# 4_Wifi_ESP32_Antenna.net
KiCad netlist of a schematic drawn in Altium Designer
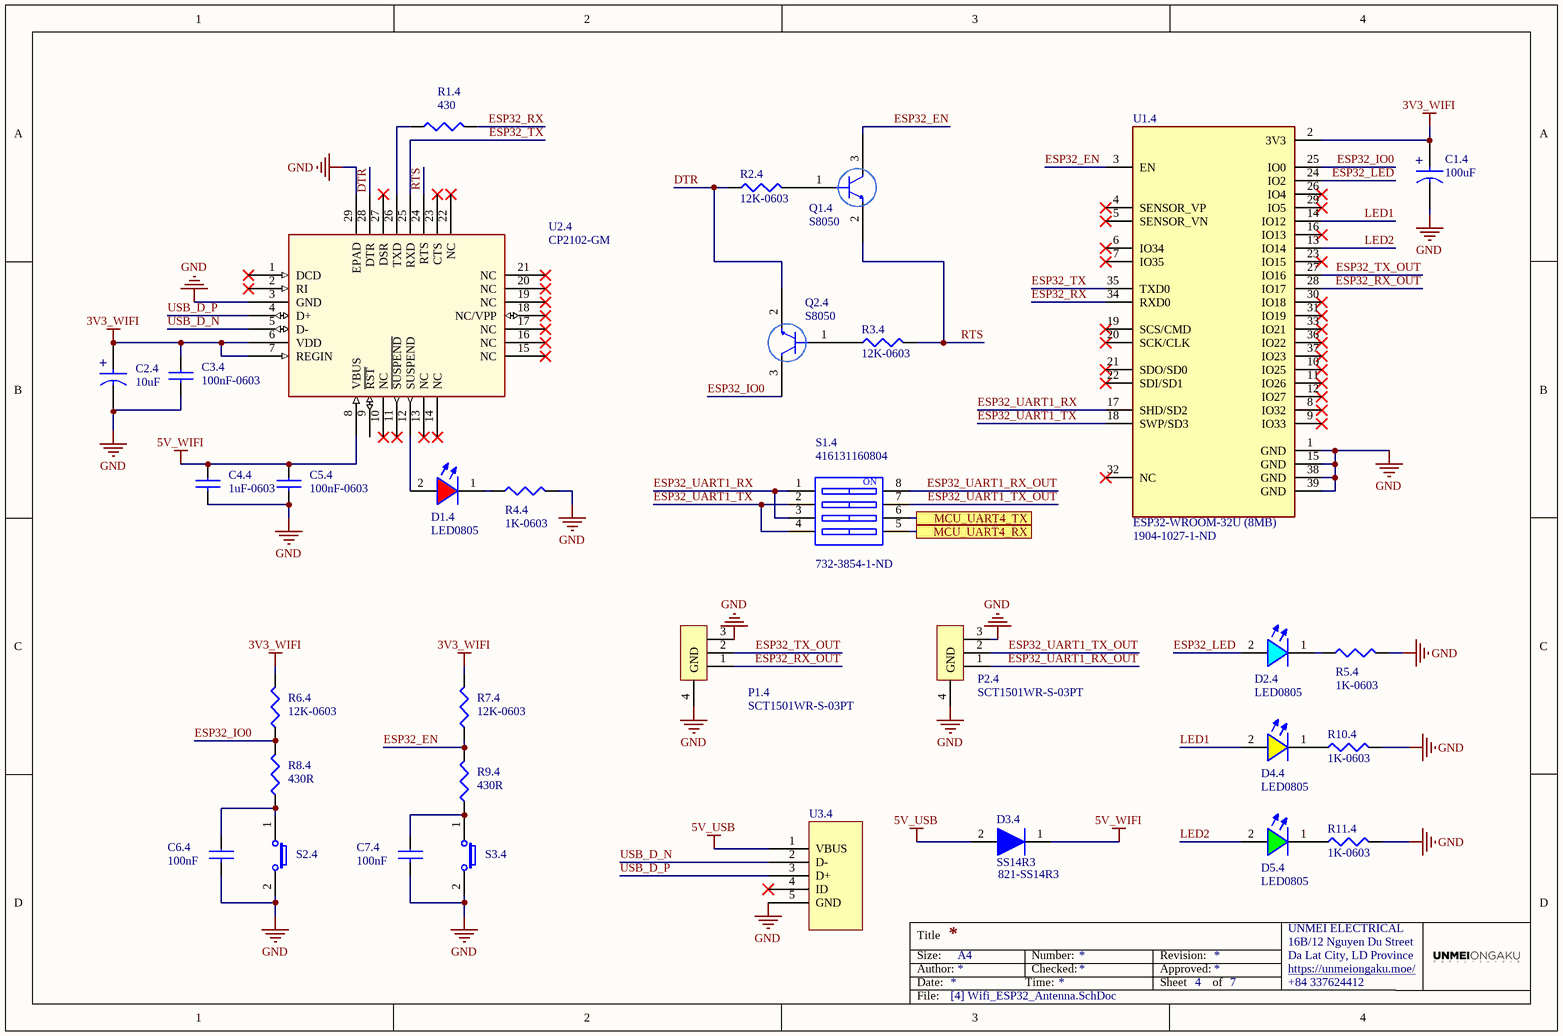
[diagram p0: [4] Wifi_ESP32_Antenna.SchDoc]

(export (version "E")
  (design (tool "Eeschema 10.0.6"))
  (components
    (comp (ref "C1.4")
      (value "100uF")
      (footprint "Capacitor/Tantalum  - SMD6032/C - AVX")
      (description "钽电容 100uF ±10% 6.3V 0.9Ω C型6032")
      (fields
        (field (name "MANUFACTURER") "Kyocera AVX")
        (field (name "MANUFACTURER PART NUMBER") "TAJC107K006RNJ")
      )
      (libsource (lib "Minh_Lib") (part "TAJC107K006RNJ"))
    )
    (comp (ref "C2.4")
      (value "10uF")
      (footprint "Capacitor/Tantalum  - SMD3528/B - AVX")
      (description "钽电容 10uF ±10% 16V 2.8Ω B型3528")
      (fields
        (field (name "MANUFACTURER") "Kyocera AVX")
        (field (name "MANUFACTURER PART NUMBER") "TAJB106K016RNJ")
      )
      (libsource (lib "Minh_Lib") (part "TAJB106K016RNJ"))
    )
    (comp (ref "C3.4")
      (value "100nF-0603")
      (footprint "CAP0603")
      (description "CAP CER 0.1UF 50V X7R 0603")
      (fields (field (name "TOLERANCE") "±10%"))
      (libsource (lib "Minh_Lib") (part "CC0603KRX7R9BB104"))
    )
    (comp (ref "C4.4")
      (value "1uF-0603")
      (footprint "CAP0603")
      (description "CAP CER 1UF 16V X7R 0603")
      (fields (field (name "TOLERANCE") "±10%"))
      (libsource (lib "Minh_Lib") (part "CC0603KRX7R7BB105"))
    )
    (comp (ref "C5.4")
      (value "100nF-0603")
      (footprint "CAP0603")
      (description "CAP CER 0.1UF 50V X7R 0603")
      (fields (field (name "TOLERANCE") "±10%"))
      (libsource (lib "Minh_Lib") (part "CC0603KRX7R9BB104"))
    )
    (comp (ref "C6.4")
      (value "100nF")
      (footprint "CAP0603")
      (description "CAP CER 0.1UF 50V X7R 0603")
      (fields (field (name "TOLERANCE") "±10%"))
      (libsource (lib "Minh_Lib") (part "CC0603KRX7R9BB104"))
    )
    (comp (ref "C7.4")
      (value "100nF")
      (footprint "CAP0603")
      (description "CAP CER 0.1UF 50V X7R 0603")
      (fields (field (name "TOLERANCE") "±10%"))
      (libsource (lib "Minh_Lib") (part "CC0603KRX7R9BB104"))
    )
    (comp (ref "D1.4")
      (value "LED0805")
      (footprint "LED0805-RED")
      (libsource (lib "Minh_Lib") (part "LED0805-RED"))
    )
    (comp (ref "D2.4")
      (value "LED0805")
      (footprint "LED0805-BLUE")
      (libsource (lib "Minh_Lib") (part "LED0805-BLUE"))
    )
    (comp (ref "D3.4")
      (value "SS14R3")
      (footprint "SS14 - 1N5819 / DO-214AA, SMA")
      (description "1A, 40V, Schottky Rectifier")
      (fields
        (field (name "MANUFACTURER") "Taiwan Semiconductor")
        (field (name "SUPPLIER PART NUMBER 1") "821-SS14R3")
      )
      (libsource (lib "Minh_Lib") (part "SS14R3"))
    )
    (comp (ref "D4.4")
      (value "LED0805")
      (footprint "LED0805-YELLOW")
      (libsource (lib "Minh_Lib") (part "LED0805-YELLOW"))
    )
    (comp (ref "D5.4")
      (value "LED0805")
      (footprint "LED0805-GREEN")
      (libsource (lib "Minh_Lib") (part "LED0805-GREEN"))
    )
    (comp (ref "P1.4")
      (value "SCT1501WR-S-03PT")
      (footprint "Connector ZH1.5 3P SMD")
      (libsource (lib "Minh_Lib") (part "SCT1501WR-S-03PT"))
    )
    (comp (ref "P2.4")
      (value "SCT1501WR-S-03PT")
      (footprint "Connector ZH1.5 3P SMD")
      (libsource (lib "Minh_Lib") (part "SCT1501WR-S-03PT"))
    )
    (comp (ref "Q1.4")
      (value "S8050")
      (footprint "SOT23")
      (description "Trans Gp Bjt NPN 25V 0.5A 3-PIN SOT-23 T/r")
      (fields (field (name "MANUFACTURER") "MCC") (field (name "MANUFACTURER PART NUMBER") "MMS8050-H-TP"))
      (libsource (lib "Minh_Lib") (part "MMS8050-H-TP"))
    )
    (comp (ref "Q2.4")
      (value "S8050")
      (footprint "SOT23")
      (description "Trans Gp Bjt NPN 25V 0.5A 3-PIN SOT-23 T/r")
      (fields (field (name "MANUFACTURER") "MCC") (field (name "MANUFACTURER PART NUMBER") "MMS8050-H-TP"))
      (libsource (lib "Minh_Lib") (part "MMS8050-H-TP"))
    )
    (comp (ref "R1.4")
      (value "430")
      (footprint "RES0603 - 3D")
      (description "Res Thick Film 0603 430 Ohm 5% 0.1W(1/10W) ±100ppm/C Pad SMD T/R")
      (fields
        (field (name "MANUFACTURER") "Yageo")
        (field (name "MANUFACTURER PART NUMBER") "RC0603JR-07430RL")
      )
      (libsource (lib "Minh_Lib") (part "RC0603JR-07430RL"))
    )
    (comp (ref "R2.4")
      (value "12K-0603")
      (footprint "RES0603 - 3D")
      (description "Thick Film Resistors - SMD 12K OHM 5%")
      (fields
        (field (name "MANUFACTURER") "Yageo")
        (field (name "MANUFACTURER PART NUMBER") "RC0603JR-0712KL")
      )
      (libsource (lib "Minh_Lib") (part "RC0603JR-0712KL"))
    )
    (comp (ref "R3.4")
      (value "12K-0603")
      (footprint "RES0603 - 3D")
      (description "Thick Film Resistors - SMD 12K OHM 5%")
      (fields
        (field (name "MANUFACTURER") "Yageo")
        (field (name "MANUFACTURER PART NUMBER") "RC0603JR-0712KL")
      )
      (libsource (lib "Minh_Lib") (part "RC0603JR-0712KL"))
    )
    (comp (ref "R4.4")
      (value "1K-0603")
      (footprint "RES0603 - 3D")
      (description "RES SMD 1K OHM 5% 1/10W 0603")
      (fields (field (name "TOLERANCE") "±5%"))
      (libsource (lib "Minh_Lib") (part "RC0603JR-071KL"))
    )
    (comp (ref "R5.4")
      (value "1K-0603")
      (footprint "RES0603 - 3D")
      (description "RES SMD 1K OHM 5% 1/10W 0603")
      (fields (field (name "TOLERANCE") "±5%"))
      (libsource (lib "Minh_Lib") (part "RC0603JR-071KL"))
    )
    (comp (ref "R6.4")
      (value "12K-0603")
      (footprint "RES0603 - 3D")
      (description "Thick Film Resistors - SMD 12K OHM 5%")
      (fields
        (field (name "MANUFACTURER") "Yageo")
        (field (name "MANUFACTURER PART NUMBER") "RC0603JR-0712KL")
      )
      (libsource (lib "Minh_Lib") (part "RC0603JR-0712KL"))
    )
    (comp (ref "R7.4")
      (value "12K-0603")
      (footprint "RES0603 - 3D")
      (description "Thick Film Resistors - SMD 12K OHM 5%")
      (fields
        (field (name "MANUFACTURER") "Yageo")
        (field (name "MANUFACTURER PART NUMBER") "RC0603JR-0712KL")
      )
      (libsource (lib "Minh_Lib") (part "RC0603JR-0712KL"))
    )
    (comp (ref "R8.4")
      (value "430R")
      (footprint "RES0603 - 3D")
      (description "Res Thick Film 0603 430 Ohm 5% 0.1W(1/10W) ±100ppm/C Pad SMD T/R")
      (fields
        (field (name "MANUFACTURER") "Yageo")
        (field (name "MANUFACTURER PART NUMBER") "RC0603JR-07430RL")
      )
      (libsource (lib "Minh_Lib") (part "RC0603JR-07430RL"))
    )
    (comp (ref "R9.4")
      (value "430R")
      (footprint "RES0603 - 3D")
      (description "Res Thick Film 0603 430 Ohm 5% 0.1W(1/10W) ±100ppm/C Pad SMD T/R")
      (fields
        (field (name "MANUFACTURER") "Yageo")
        (field (name "MANUFACTURER PART NUMBER") "RC0603JR-07430RL")
      )
      (libsource (lib "Minh_Lib") (part "RC0603JR-07430RL"))
    )
    (comp (ref "R10.4")
      (value "1K-0603")
      (footprint "RES0603 - 3D")
      (description "RES SMD 1K OHM 5% 1/10W 0603")
      (fields (field (name "TOLERANCE") "±5%"))
      (libsource (lib "Minh_Lib") (part "RC0603JR-071KL"))
    )
    (comp (ref "R11.4")
      (value "1K-0603")
      (footprint "RES0603 - 3D")
      (description "RES SMD 1K OHM 5% 1/10W 0603")
      (fields (field (name "TOLERANCE") "±5%"))
      (libsource (lib "Minh_Lib") (part "RC0603JR-071KL"))
    )
    (comp (ref "S1.4")
      (value "416131160804")
      (footprint "DIP Switches SMD 1.27mm 4P")
      (description "DIP Switch Dimensions L x W x H: 5.6 x 2 mm Series: WS-DISV L: 6.12 mm Poles: 4")
      (fields
        (field (name "MANUFACTURER") "Wurth Electronics")
        (field (name "SUPPLIER PART NUMBER 1") "732-3854-1-ND")
      )
      (libsource (lib "Minh_Lib") (part "416131160804"))
    )
    (comp (ref "S2.4")
      (value "434121043816")
      (footprint "Switches-6x3.5x4.3mm")
      (description "Switch Tactile Spst-no 0.05A 12V")
      (fields (field (name "MANUFACTURER") "Wurth Electronics"))
      (libsource (lib "Minh_Lib") (part "434121043816"))
    )
    (comp (ref "S3.4")
      (value "434121043816")
      (footprint "Switches-6x3.5x4.3mm")
      (description "Switch Tactile Spst-no 0.05A 12V")
      (fields (field (name "MANUFACTURER") "Wurth Electronics"))
      (libsource (lib "Minh_Lib") (part "434121043816"))
    )
    (comp (ref "U1.4")
      (value "ESP32-WROOM-32U (8MB)")
      (footprint "ESP32 WROOM 32U")
      (description "SMD Module, ESP32-D0WD, 64MBITS Spi Flash, Uart Mode, U.fl Antenna Connector")
      (fields
        (field (name "MANUFACTURER") "Espressif Systems")
        (field (name "TOLERANCE") "0.1%")
        (field (name "SUPPLIER PART NUMBER 1") "1904-1027-1-ND")
      )
      (libsource (lib "Minh_Lib") (part "ESP32-WROOM-32U (8MB)"))
    )
    (comp (ref "U2.4")
      (value "CP2102-GM")
      (footprint "QFN28_5X5_SIL")
      (fields (field (name "COPYRIGHT") "Copyright (C) 2018 Accelerated Designs. All rights reserved"))
      (libsource (lib "Minh_Lib") (part "CP2102-GM"))
    )
    (comp (ref "U3.4")
      (value "Micro USB - UJ2-MIBH-G-SMT-TR")
      (footprint "Micro USB V2 SMD")
      (description "Conn Micro USB 2.0 Type B RCP 5 POS 0.65mm Solder RA SMD 5 Terminal 1 Port T/R")
      (fields
        (field (name "MANUFACTURER") "CUI Devices")
        (field (name "MANUFACTURER PART NUMBER") "UJ2-MIBH-G-SMT-TR")
      )
      (libsource (lib "Minh_Lib") (part "Micro USB - UJ2-MIBH-G-SMT-TR"))
    )
  )
  (nets
    (net (code "1") (name "/DTR") (class "Default")
      (node (ref "Q2.4") (pin "2") (pinfunction "2_2") (pintype "passive"))
      (node (ref "R2.4") (pin "1") (pinfunction "1_1") (pintype "passive"))
      (node (ref "U2.4") (pin "28") (pinfunction "DTR_28") (pintype "passive"))
    )
    (net (code "2") (name "/ESP32_EN") (class "Default")
      (node (ref "Q1.4") (pin "3") (pinfunction "3_3") (pintype "passive"))
      (node (ref "R7.4") (pin "1") (pinfunction "1_1") (pintype "passive"))
      (node (ref "R9.4") (pin "2") (pinfunction "2_2") (pintype "passive"))
      (node (ref "U1.4") (pin "3") (pinfunction "EN_3") (pintype "passive"))
    )
    (net (code "3") (name "/ESP32_IO0") (class "Default")
      (node (ref "Q2.4") (pin "3") (pinfunction "3_3") (pintype "passive"))
      (node (ref "R6.4") (pin "1") (pinfunction "1_1") (pintype "passive"))
      (node (ref "R8.4") (pin "2") (pinfunction "2_2") (pintype "passive"))
      (node (ref "U1.4") (pin "25") (pinfunction "IO0_25") (pintype "passive"))
    )
    (net (code "4") (name "/ESP32_LED") (class "Default")
      (node (ref "D2.4") (pin "2") (pinfunction "+_2") (pintype "passive"))
      (node (ref "U1.4") (pin "24") (pinfunction "IO2_24") (pintype "passive"))
    )
    (net (code "5") (name "/ESP32_RX") (class "Default")
      (node (ref "R1.4") (pin "2") (pinfunction "2_2") (pintype "passive"))
      (node (ref "U1.4") (pin "34") (pinfunction "RXD0_34") (pintype "passive"))
    )
    (net (code "6") (name "/ESP32_RX_OUT") (class "Default")
      (node (ref "P1.4") (pin "1") (pinfunction "1_1") (pintype "passive"))
      (node (ref "U1.4") (pin "28") (pinfunction "IO17_28") (pintype "passive"))
    )
    (net (code "7") (name "/ESP32_TX") (class "Default")
      (node (ref "U1.4") (pin "35") (pinfunction "TXD0_35") (pintype "passive"))
      (node (ref "U2.4") (pin "25") (pinfunction "RXD_25") (pintype "passive"))
    )
    (net (code "8") (name "/ESP32_TX_OUT") (class "Default")
      (node (ref "P1.4") (pin "2") (pinfunction "2_2") (pintype "passive"))
      (node (ref "U1.4") (pin "27") (pinfunction "IO16_27") (pintype "passive"))
    )
    (net (code "9") (name "/ESP32_UART1_RX") (class "Default")
      (node (ref "S1.4") (pin "1") (pinfunction "1_1") (pintype "passive"))
      (node (ref "S1.4") (pin "3") (pinfunction "3_3") (pintype "passive"))
      (node (ref "U1.4") (pin "17") (pinfunction "SHD/SD2_17") (pintype "passive"))
    )
    (net (code "10") (name "/ESP32_UART1_RX_OUT") (class "Default")
      (node (ref "P2.4") (pin "1") (pinfunction "1_1") (pintype "passive"))
      (node (ref "S1.4") (pin "8") (pinfunction "8_8") (pintype "passive"))
    )
    (net (code "11") (name "/ESP32_UART1_TX") (class "Default")
      (node (ref "S1.4") (pin "2") (pinfunction "2_2") (pintype "passive"))
      (node (ref "S1.4") (pin "4") (pinfunction "4_4") (pintype "passive"))
      (node (ref "U1.4") (pin "18") (pinfunction "SWP/SD3_18") (pintype "passive"))
    )
    (net (code "12") (name "/ESP32_UART1_TX_OUT") (class "Default")
      (node (ref "P2.4") (pin "2") (pinfunction "2_2") (pintype "passive"))
      (node (ref "S1.4") (pin "7") (pinfunction "7_7") (pintype "passive"))
    )
    (net (code "13") (name "/LED1") (class "Default")
      (node (ref "D4.4") (pin "2") (pinfunction "+_2") (pintype "passive"))
      (node (ref "U1.4") (pin "14") (pinfunction "IO12_14") (pintype "passive"))
    )
    (net (code "14") (name "/LED2") (class "Default")
      (node (ref "D5.4") (pin "2") (pinfunction "+_2") (pintype "passive"))
      (node (ref "U1.4") (pin "13") (pinfunction "IO14_13") (pintype "passive"))
    )
    (net (code "15") (name "/MCU_UART4_RX") (class "Default")
      (node (ref "S1.4") (pin "5") (pinfunction "5_5") (pintype "passive"))
    )
    (net (code "16") (name "/MCU_UART4_TX") (class "Default")
      (node (ref "S1.4") (pin "6") (pinfunction "6_6") (pintype "passive"))
    )
    (net (code "17") (name "/RTS") (class "Default")
      (node (ref "Q1.4") (pin "2") (pinfunction "2_2") (pintype "passive"))
      (node (ref "R3.4") (pin "2") (pinfunction "2_2") (pintype "passive"))
      (node (ref "U2.4") (pin "24") (pinfunction "RTS_24") (pintype "passive"))
    )
    (net (code "18") (name "/USB_D_N") (class "Default")
      (node (ref "U2.4") (pin "5") (pinfunction "D-_5") (pintype "bidirectional"))
      (node (ref "U3.4") (pin "2") (pinfunction "D-_2") (pintype "passive"))
    )
    (net (code "19") (name "/USB_D_P") (class "Default")
      (node (ref "U2.4") (pin "4") (pinfunction "D+_4") (pintype "bidirectional"))
      (node (ref "U3.4") (pin "3") (pinfunction "D+_3") (pintype "passive"))
    )
    (net (code "20") (name "3V3_WIFI") (class "Default")
      (node (ref "C1.4") (pin "1") (pinfunction "1_1") (pintype "passive"))
      (node (ref "C2.4") (pin "1") (pinfunction "1_1") (pintype "passive"))
      (node (ref "C3.4") (pin "1") (pinfunction "1_1") (pintype "passive"))
      (node (ref "R6.4") (pin "2") (pinfunction "2_2") (pintype "passive"))
      (node (ref "R7.4") (pin "2") (pinfunction "2_2") (pintype "passive"))
      (node (ref "U1.4") (pin "2") (pinfunction "3V3_2") (pintype "power_in"))
      (node (ref "U2.4") (pin "6") (pinfunction "VDD_6") (pintype "power_in"))
      (node (ref "U2.4") (pin "7") (pinfunction "REGIN_7") (pintype "input"))
    )
    (net (code "21") (name "5V_USB") (class "Default")
      (node (ref "D3.4") (pin "2") (pintype "passive"))
      (node (ref "U3.4") (pin "1") (pinfunction "VBUS_1") (pintype "passive"))
    )
    (net (code "22") (name "5V_WIFI") (class "Default")
      (node (ref "C4.4") (pin "1") (pinfunction "1_1") (pintype "passive"))
      (node (ref "C5.4") (pin "1") (pinfunction "1_1") (pintype "passive"))
      (node (ref "D3.4") (pin "1") (pintype "passive"))
      (node (ref "U2.4") (pin "8") (pinfunction "VBUS_8") (pintype "input"))
    )
    (net (code "23") (name "GND") (class "Default")
      (node (ref "C1.4") (pin "2") (pinfunction "2_2") (pintype "passive"))
      (node (ref "C2.4") (pin "2") (pinfunction "2_2") (pintype "passive"))
      (node (ref "C3.4") (pin "2") (pinfunction "2_2") (pintype "passive"))
      (node (ref "C4.4") (pin "2") (pinfunction "2_2") (pintype "passive"))
      (node (ref "C5.4") (pin "2") (pinfunction "2_2") (pintype "passive"))
      (node (ref "C6.4") (pin "2") (pinfunction "2_2") (pintype "passive"))
      (node (ref "C7.4") (pin "2") (pinfunction "2_2") (pintype "passive"))
      (node (ref "P1.4") (pin "3") (pinfunction "3_3") (pintype "passive"))
      (node (ref "P1.4") (pin "4") (pinfunction "GND_4") (pintype "passive"))
      (node (ref "P2.4") (pin "3") (pinfunction "3_3") (pintype "passive"))
      (node (ref "P2.4") (pin "4") (pinfunction "GND_4") (pintype "passive"))
      (node (ref "R10.4") (pin "2") (pinfunction "2_2") (pintype "passive"))
      (node (ref "R11.4") (pin "2") (pinfunction "2_2") (pintype "passive"))
      (node (ref "R4.4") (pin "2") (pinfunction "2_2") (pintype "passive"))
      (node (ref "R5.4") (pin "2") (pinfunction "2_2") (pintype "passive"))
      (node (ref "S2.4") (pin "2") (pinfunction "2_2") (pintype "passive"))
      (node (ref "S3.4") (pin "2") (pinfunction "2_2") (pintype "passive"))
      (node (ref "U1.4") (pin "1") (pinfunction "GND_1") (pintype "power_in"))
      (node (ref "U1.4") (pin "15") (pinfunction "GND_15") (pintype "power_in"))
      (node (ref "U1.4") (pin "38") (pinfunction "GND_38") (pintype "power_in"))
      (node (ref "U1.4") (pin "39") (pinfunction "GND_39") (pintype "power_in"))
      (node (ref "U2.4") (pin "29") (pinfunction "EPAD_29") (pintype "passive"))
      (node (ref "U2.4") (pin "3") (pinfunction "GND_3") (pintype "power_in"))
      (node (ref "U3.4") (pin "5") (pinfunction "GND_5") (pintype "passive"))
    )
    (net (code "24") (name "Net-(C6.4-Pad1)") (class "Default")
      (node (ref "C6.4") (pin "1") (pinfunction "1_1") (pintype "passive"))
      (node (ref "R8.4") (pin "1") (pinfunction "1_1") (pintype "passive"))
      (node (ref "S2.4") (pin "1") (pinfunction "1_1") (pintype "passive"))
    )
    (net (code "25") (name "Net-(C7.4-Pad1)") (class "Default")
      (node (ref "C7.4") (pin "1") (pinfunction "1_1") (pintype "passive"))
      (node (ref "R9.4") (pin "1") (pinfunction "1_1") (pintype "passive"))
      (node (ref "S3.4") (pin "1") (pinfunction "1_1") (pintype "passive"))
    )
    (net (code "26") (name "Net-(D1.4-+-Pad1)") (class "Default")
      (node (ref "D1.4") (pin "1") (pinfunction "+_1") (pintype "passive"))
      (node (ref "R4.4") (pin "1") (pinfunction "1_1") (pintype "passive"))
    )
    (net (code "27") (name "Net-(D2.4-+-Pad1)") (class "Default")
      (node (ref "D2.4") (pin "1") (pinfunction "+_1") (pintype "passive"))
      (node (ref "R5.4") (pin "1") (pinfunction "1_1") (pintype "passive"))
    )
    (net (code "28") (name "Net-(D4.4-+-Pad1)") (class "Default")
      (node (ref "D4.4") (pin "1") (pinfunction "+_1") (pintype "passive"))
      (node (ref "R10.4") (pin "1") (pinfunction "1_1") (pintype "passive"))
    )
    (net (code "29") (name "Net-(D5.4-+-Pad1)") (class "Default")
      (node (ref "D5.4") (pin "1") (pinfunction "+_1") (pintype "passive"))
      (node (ref "R11.4") (pin "1") (pinfunction "1_1") (pintype "passive"))
    )
    (net (code "30") (name "Net-(Q1.4-Pad1)") (class "Default")
      (node (ref "Q1.4") (pin "1") (pinfunction "1_1") (pintype "passive"))
      (node (ref "R2.4") (pin "2") (pinfunction "2_2") (pintype "passive"))
    )
    (net (code "31") (name "Net-(Q2.4-Pad1)") (class "Default")
      (node (ref "Q2.4") (pin "1") (pinfunction "1_1") (pintype "passive"))
      (node (ref "R3.4") (pin "1") (pinfunction "1_1") (pintype "passive"))
    )
    (net (code "32") (name "Net-(U2.4-SUSPEND)") (class "Default")
      (node (ref "D1.4") (pin "2") (pinfunction "+_2") (pintype "passive"))
      (node (ref "U2.4") (pin "12") (pinfunction "SUSPEND_12") (pintype "output"))
    )
    (net (code "33") (name "Net-(U2.4-TXD)") (class "Default")
      (node (ref "R1.4") (pin "1") (pinfunction "1_1") (pintype "passive"))
      (node (ref "U2.4") (pin "26") (pinfunction "TXD_26") (pintype "passive"))
    )
    (net (code "34") (name "unconnected-(U1.4-IO4-Pad26)") (class "Default")
      (node (ref "U1.4") (pin "26") (pinfunction "IO4_26") (pintype "passive+no_connect"))
    )
    (net (code "35") (name "unconnected-(U1.4-IO5-Pad29)") (class "Default")
      (node (ref "U1.4") (pin "29") (pinfunction "IO5_29") (pintype "passive+no_connect"))
    )
    (net (code "36") (name "unconnected-(U1.4-IO13-Pad16)") (class "Default")
      (node (ref "U1.4") (pin "16") (pinfunction "IO13_16") (pintype "passive+no_connect"))
    )
    (net (code "37") (name "unconnected-(U1.4-IO15-Pad23)") (class "Default")
      (node (ref "U1.4") (pin "23") (pinfunction "IO15_23") (pintype "passive+no_connect"))
    )
    (net (code "38") (name "unconnected-(U1.4-IO18-Pad30)") (class "Default")
      (node (ref "U1.4") (pin "30") (pinfunction "IO18_30") (pintype "passive+no_connect"))
    )
    (net (code "39") (name "unconnected-(U1.4-IO19-Pad31)") (class "Default")
      (node (ref "U1.4") (pin "31") (pinfunction "IO19_31") (pintype "passive+no_connect"))
    )
    (net (code "40") (name "unconnected-(U1.4-IO21-Pad33)") (class "Default")
      (node (ref "U1.4") (pin "33") (pinfunction "IO21_33") (pintype "passive+no_connect"))
    )
    (net (code "41") (name "unconnected-(U1.4-IO22-Pad36)") (class "Default")
      (node (ref "U1.4") (pin "36") (pinfunction "IO22_36") (pintype "passive+no_connect"))
    )
    (net (code "42") (name "unconnected-(U1.4-IO23-Pad37)") (class "Default")
      (node (ref "U1.4") (pin "37") (pinfunction "IO23_37") (pintype "passive+no_connect"))
    )
    (net (code "43") (name "unconnected-(U1.4-IO25-Pad10)") (class "Default")
      (node (ref "U1.4") (pin "10") (pinfunction "IO25_10") (pintype "passive+no_connect"))
    )
    (net (code "44") (name "unconnected-(U1.4-IO26-Pad11)") (class "Default")
      (node (ref "U1.4") (pin "11") (pinfunction "IO26_11") (pintype "passive+no_connect"))
    )
    (net (code "45") (name "unconnected-(U1.4-IO27-Pad12)") (class "Default")
      (node (ref "U1.4") (pin "12") (pinfunction "IO27_12") (pintype "passive+no_connect"))
    )
    (net (code "46") (name "unconnected-(U1.4-IO32-Pad8)") (class "Default")
      (node (ref "U1.4") (pin "8") (pinfunction "IO32_8") (pintype "passive+no_connect"))
    )
    (net (code "47") (name "unconnected-(U1.4-IO33-Pad9)") (class "Default")
      (node (ref "U1.4") (pin "9") (pinfunction "IO33_9") (pintype "passive+no_connect"))
    )
    (net (code "48") (name "unconnected-(U1.4-IO34-Pad6)") (class "Default")
      (node (ref "U1.4") (pin "6") (pinfunction "IO34_6") (pintype "passive+no_connect"))
    )
    (net (code "49") (name "unconnected-(U1.4-IO35-Pad7)") (class "Default")
      (node (ref "U1.4") (pin "7") (pinfunction "IO35_7") (pintype "passive+no_connect"))
    )
    (net (code "50") (name "unconnected-(U1.4-NC-Pad32)") (class "Default")
      (node (ref "U1.4") (pin "32") (pinfunction "NC_32") (pintype "passive+no_connect"))
    )
    (net (code "51") (name "unconnected-(U1.4-SCK{slash}CLK-Pad20)") (class "Default")
      (node (ref "U1.4") (pin "20") (pinfunction "SCK/CLK_20") (pintype "passive+no_connect"))
    )
    (net (code "52") (name "unconnected-(U1.4-SCS{slash}CMD-Pad19)") (class "Default")
      (node (ref "U1.4") (pin "19") (pinfunction "SCS/CMD_19") (pintype "passive+no_connect"))
    )
    (net (code "53") (name "unconnected-(U1.4-SDI{slash}SD1-Pad22)") (class "Default")
      (node (ref "U1.4") (pin "22") (pinfunction "SDI/SD1_22") (pintype "passive+no_connect"))
    )
    (net (code "54") (name "unconnected-(U1.4-SDO{slash}SD0-Pad21)") (class "Default")
      (node (ref "U1.4") (pin "21") (pinfunction "SDO/SD0_21") (pintype "passive+no_connect"))
    )
    (net (code "55") (name "unconnected-(U1.4-SENSOR_VN-Pad5)") (class "Default")
      (node (ref "U1.4") (pin "5") (pinfunction "SENSOR_VN_5") (pintype "passive+no_connect"))
    )
    (net (code "56") (name "unconnected-(U1.4-SENSOR_VP-Pad4)") (class "Default")
      (node (ref "U1.4") (pin "4") (pinfunction "SENSOR_VP_4") (pintype "passive+no_connect"))
    )
    (net (code "57") (name "unconnected-(U2.4-CTS-Pad23)") (class "Default")
      (node (ref "U2.4") (pin "23") (pinfunction "CTS_23") (pintype "passive+no_connect"))
    )
    (net (code "58") (name "unconnected-(U2.4-DCD-Pad1)") (class "Default")
      (node (ref "U2.4") (pin "1") (pinfunction "DCD_1") (pintype "input+no_connect"))
    )
    (net (code "59") (name "unconnected-(U2.4-DSR-Pad27)") (class "Default")
      (node (ref "U2.4") (pin "27") (pinfunction "DSR_27") (pintype "passive+no_connect"))
    )
    (net (code "60") (name "unconnected-(U2.4-NC-Pad10)") (class "Default")
      (node (ref "U2.4") (pin "10") (pinfunction "NC_10") (pintype "passive+no_connect"))
    )
    (net (code "61") (name "unconnected-(U2.4-NC-Pad13)") (class "Default")
      (node (ref "U2.4") (pin "13") (pinfunction "NC_13") (pintype "passive+no_connect"))
    )
    (net (code "62") (name "unconnected-(U2.4-NC-Pad14)") (class "Default")
      (node (ref "U2.4") (pin "14") (pinfunction "NC_14") (pintype "passive+no_connect"))
    )
    (net (code "63") (name "unconnected-(U2.4-NC-Pad15)") (class "Default")
      (node (ref "U2.4") (pin "15") (pinfunction "NC_15") (pintype "passive+no_connect"))
    )
    (net (code "64") (name "unconnected-(U2.4-NC-Pad16)") (class "Default")
      (node (ref "U2.4") (pin "16") (pinfunction "NC_16") (pintype "passive+no_connect"))
    )
    (net (code "65") (name "unconnected-(U2.4-NC-Pad17)") (class "Default")
      (node (ref "U2.4") (pin "17") (pinfunction "NC_17") (pintype "passive+no_connect"))
    )
    (net (code "66") (name "unconnected-(U2.4-NC-Pad19)") (class "Default")
      (node (ref "U2.4") (pin "19") (pinfunction "NC_19") (pintype "passive+no_connect"))
    )
    (net (code "67") (name "unconnected-(U2.4-NC-Pad20)") (class "Default")
      (node (ref "U2.4") (pin "20") (pinfunction "NC_20") (pintype "passive+no_connect"))
    )
    (net (code "68") (name "unconnected-(U2.4-NC-Pad21)") (class "Default")
      (node (ref "U2.4") (pin "21") (pinfunction "NC_21") (pintype "passive+no_connect"))
    )
    (net (code "69") (name "unconnected-(U2.4-NC-Pad22)") (class "Default")
      (node (ref "U2.4") (pin "22") (pinfunction "NC_22") (pintype "passive+no_connect"))
    )
    (net (code "70") (name "unconnected-(U2.4-NC{slash}VPP-Pad18)") (class "Default")
      (node (ref "U2.4") (pin "18") (pinfunction "NC/VPP_18") (pintype "bidirectional+no_connect"))
    )
    (net (code "71") (name "unconnected-(U2.4-RI-Pad2)") (class "Default")
      (node (ref "U2.4") (pin "2") (pinfunction "RI_2") (pintype "input+no_connect"))
    )
    (net (code "72") (name "unconnected-(U2.4-~{RST}-Pad9)") (class "Default")
      (node (ref "U2.4") (pin "9") (pinfunction "~{RST}_9") (pintype "bidirectional"))
    )
    (net (code "73") (name "unconnected-(U2.4-~{SUSPEND}-Pad11)") (class "Default")
      (node (ref "U2.4") (pin "11") (pinfunction "~{SUSPEND}_11") (pintype "output+no_connect"))
    )
    (net (code "74") (name "unconnected-(U3.4-ID-Pad4)") (class "Default")
      (node (ref "U3.4") (pin "4") (pinfunction "ID_4") (pintype "passive+no_connect"))
    )
  )
)
